# remote.net
KiCad netlist of a schematic drawn in EAGLE
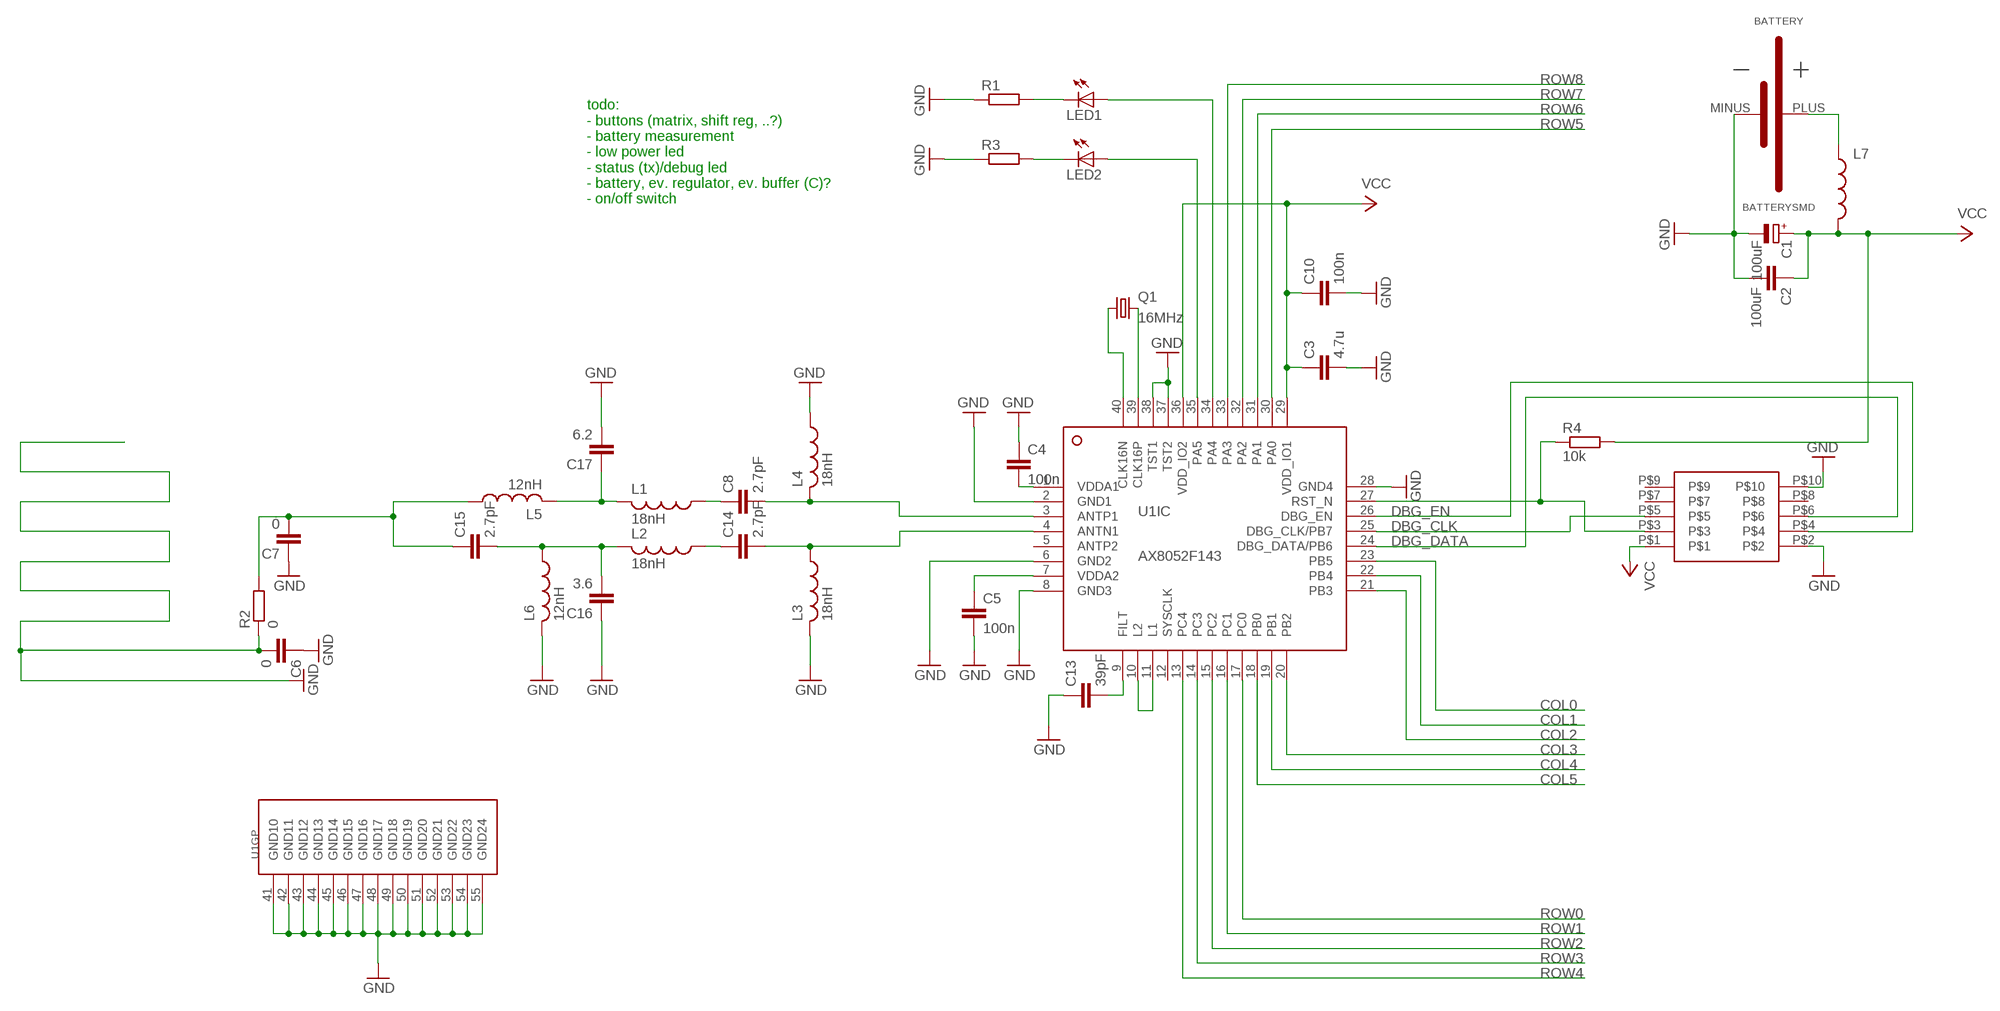
[diagram p0: schematic, sheet 1, part 1 of 2]
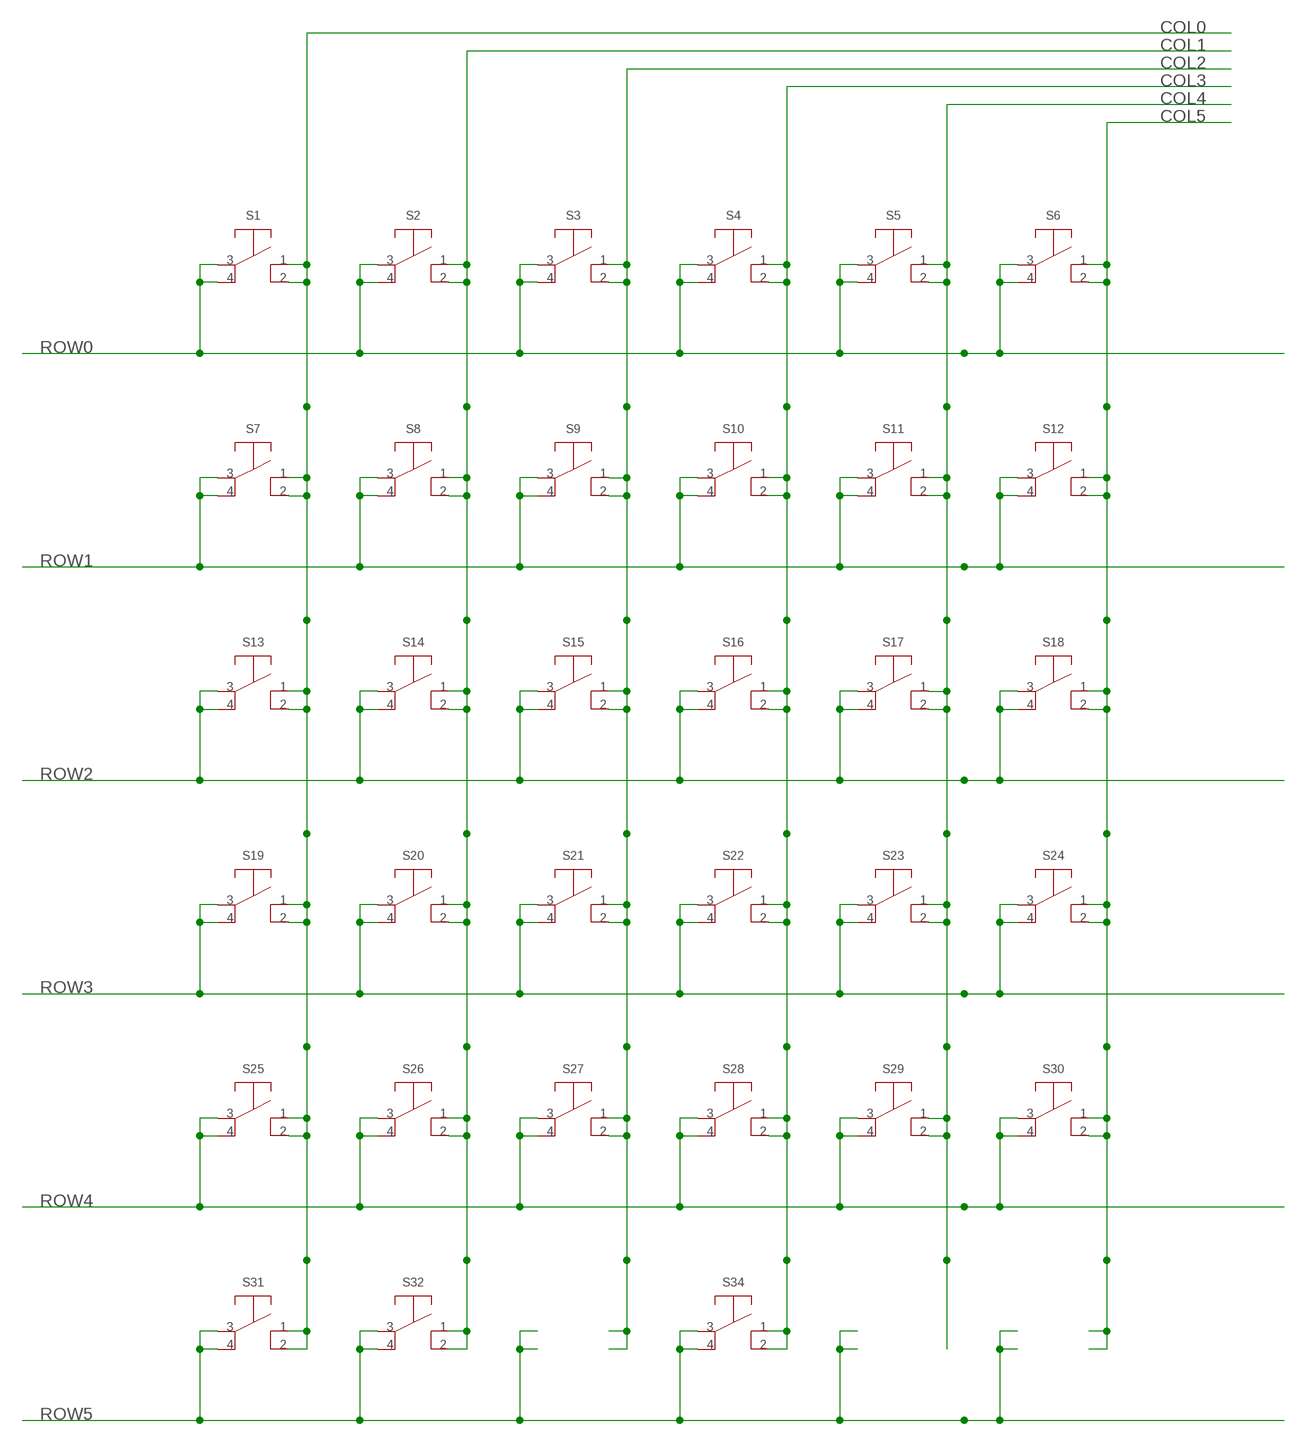
[diagram p1: schematic, sheet 1, part 2 of 2]

(export (version "E")
  (design (tool "Eeschema 10.0.6"))
  (components
    (comp (ref "BATTERY")
      (value "BATTERYSMD")
      (footprint "eagle-import:CR2032-SMD")
      (libsource (lib "eagle-import") (part "BATTERYSMD"))
    )
    (comp (ref "C1")
      (value "100uF")
      (footprint "eagle-import:PANASONIC_E")
      (libsource (lib "eagle-import") (part "CPOL-EUE"))
    )
    (comp (ref "C2")
      (value "100uF")
      (footprint "eagle-import:C1206K")
      (libsource (lib "eagle-import") (part "C-EUC1206K"))
    )
    (comp (ref "C3")
      (value "4.7u")
      (footprint "eagle-import:C0805")
      (libsource (lib "eagle-import") (part "C-EUC0805"))
    )
    (comp (ref "C4")
      (value "100n")
      (footprint "eagle-import:C0603")
      (libsource (lib "eagle-import") (part "C-EUC0603"))
    )
    (comp (ref "C5")
      (value "100n")
      (footprint "eagle-import:C0603")
      (libsource (lib "eagle-import") (part "C-EUC0603"))
    )
    (comp (ref "C6")
      (value "0")
      (footprint "eagle-import:C0805")
      (libsource (lib "eagle-import") (part "C-EUC0805"))
    )
    (comp (ref "C7")
      (value "0")
      (footprint "eagle-import:C0805")
      (libsource (lib "eagle-import") (part "C-EUC0805"))
    )
    (comp (ref "C8")
      (value "2.7pF")
      (footprint "eagle-import:C0805")
      (libsource (lib "eagle-import") (part "C-EUC0805"))
    )
    (comp (ref "C10")
      (value "100n")
      (footprint "eagle-import:C0603")
      (libsource (lib "eagle-import") (part "C-EUC0603"))
    )
    (comp (ref "C13")
      (value "39pF")
      (footprint "eagle-import:C0805")
      (libsource (lib "eagle-import") (part "C-EUC0805"))
    )
    (comp (ref "C14")
      (value "2.7pF")
      (footprint "eagle-import:C0805")
      (libsource (lib "eagle-import") (part "C-EUC0805"))
    )
    (comp (ref "C15")
      (value "2.7pF")
      (footprint "eagle-import:C0805")
      (libsource (lib "eagle-import") (part "C-EUC0805"))
    )
    (comp (ref "C16")
      (value "3.6")
      (footprint "eagle-import:C0805")
      (libsource (lib "eagle-import") (part "C-EUC0805"))
    )
    (comp (ref "C17")
      (value "6.2")
      (footprint "eagle-import:C0805")
      (libsource (lib "eagle-import") (part "C-EUC0805"))
    )
    (comp (ref "L1")
      (value "18nH")
      (footprint "eagle-import:C0603")
      (libsource (lib "eagle-import") (part "L-US0603"))
    )
    (comp (ref "L2")
      (value "18nH")
      (footprint "eagle-import:C0603")
      (libsource (lib "eagle-import") (part "L-US0603"))
    )
    (comp (ref "L3")
      (value "18nH")
      (footprint "eagle-import:C0603")
      (libsource (lib "eagle-import") (part "L-US0603"))
    )
    (comp (ref "L4")
      (value "18nH")
      (footprint "eagle-import:C0603")
      (libsource (lib "eagle-import") (part "L-US0603"))
    )
    (comp (ref "L5")
      (value "12nH")
      (footprint "eagle-import:C0603")
      (libsource (lib "eagle-import") (part "L-US0603"))
    )
    (comp (ref "L6")
      (value "12nH")
      (footprint "eagle-import:C0603")
      (libsource (lib "eagle-import") (part "L-US0603"))
    )
    (comp (ref "L7")
      (value "INDUCTORNPI75")
      (footprint "eagle-import:NPI75C")
      (libsource (lib "eagle-import") (part "INDUCTORNPI75"))
    )
    (comp (ref "LED1")
      (value "LEDCHIPLED_1206")
      (footprint "eagle-import:CHIPLED_1206")
      (libsource (lib "eagle-import") (part "LEDCHIPLED_1206"))
    )
    (comp (ref "LED2")
      (value "LEDCHIPLED_1206")
      (footprint "eagle-import:CHIPLED_1206")
      (libsource (lib "eagle-import") (part "LEDCHIPLED_1206"))
    )
    (comp (ref "Q1")
      (value "16MHz")
      (footprint "eagle-import:SM49")
      (libsource (lib "eagle-import") (part "CRYSTALSM49"))
    )
    (comp (ref "R1")
      (value "R-EU_R0603")
      (footprint "eagle-import:R0603")
      (libsource (lib "eagle-import") (part "R-EU_R0603"))
    )
    (comp (ref "R2")
      (value "0")
      (footprint "eagle-import:R0603")
      (libsource (lib "eagle-import") (part "R-EU_R0603"))
    )
    (comp (ref "R3")
      (value "R-EU_R0603")
      (footprint "eagle-import:R0603")
      (libsource (lib "eagle-import") (part "R-EU_R0603"))
    )
    (comp (ref "R4")
      (value "10k")
      (footprint "eagle-import:R0603")
      (libsource (lib "eagle-import") (part "R-EU_R0603"))
    )
    (comp (ref "S1")
      (value "SWITCHSMD")
      (footprint "eagle-import:TACTILE_SWITCH_FSM2JSMA")
      (libsource (lib "eagle-import") (part "SWITCHSMD"))
    )
    (comp (ref "S2")
      (value "SWITCHSMD")
      (footprint "eagle-import:TACTILE_SWITCH_FSM2JSMA")
      (libsource (lib "eagle-import") (part "SWITCHSMD"))
    )
    (comp (ref "S3")
      (value "SWITCHSMD")
      (footprint "eagle-import:TACTILE_SWITCH_FSM2JSMA")
      (libsource (lib "eagle-import") (part "SWITCHSMD"))
    )
    (comp (ref "S4")
      (value "SWITCHSMD")
      (footprint "eagle-import:TACTILE_SWITCH_FSM2JSMA")
      (libsource (lib "eagle-import") (part "SWITCHSMD"))
    )
    (comp (ref "S5")
      (value "SWITCHSMD")
      (footprint "eagle-import:TACTILE_SWITCH_FSM2JSMA")
      (libsource (lib "eagle-import") (part "SWITCHSMD"))
    )
    (comp (ref "S6")
      (value "SWITCHSMD")
      (footprint "eagle-import:TACTILE_SWITCH_FSM2JSMA")
      (libsource (lib "eagle-import") (part "SWITCHSMD"))
    )
    (comp (ref "S7")
      (value "SWITCHSMD")
      (footprint "eagle-import:TACTILE_SWITCH_FSM2JSMA")
      (libsource (lib "eagle-import") (part "SWITCHSMD"))
    )
    (comp (ref "S8")
      (value "SWITCHSMD")
      (footprint "eagle-import:TACTILE_SWITCH_FSM2JSMA")
      (libsource (lib "eagle-import") (part "SWITCHSMD"))
    )
    (comp (ref "S9")
      (value "SWITCHSMD")
      (footprint "eagle-import:TACTILE_SWITCH_FSM2JSMA")
      (libsource (lib "eagle-import") (part "SWITCHSMD"))
    )
    (comp (ref "S10")
      (value "SWITCHSMD")
      (footprint "eagle-import:TACTILE_SWITCH_FSM2JSMA")
      (libsource (lib "eagle-import") (part "SWITCHSMD"))
    )
    (comp (ref "S11")
      (value "SWITCHSMD")
      (footprint "eagle-import:TACTILE_SWITCH_FSM2JSMA")
      (libsource (lib "eagle-import") (part "SWITCHSMD"))
    )
    (comp (ref "S12")
      (value "SWITCHSMD")
      (footprint "eagle-import:TACTILE_SWITCH_FSM2JSMA")
      (libsource (lib "eagle-import") (part "SWITCHSMD"))
    )
    (comp (ref "S13")
      (value "SWITCHSMD")
      (footprint "eagle-import:TACTILE_SWITCH_FSM2JSMA")
      (libsource (lib "eagle-import") (part "SWITCHSMD"))
    )
    (comp (ref "S14")
      (value "SWITCHSMD")
      (footprint "eagle-import:TACTILE_SWITCH_FSM2JSMA")
      (libsource (lib "eagle-import") (part "SWITCHSMD"))
    )
    (comp (ref "S15")
      (value "SWITCHSMD")
      (footprint "eagle-import:TACTILE_SWITCH_FSM2JSMA")
      (libsource (lib "eagle-import") (part "SWITCHSMD"))
    )
    (comp (ref "S16")
      (value "SWITCHSMD")
      (footprint "eagle-import:TACTILE_SWITCH_FSM2JSMA")
      (libsource (lib "eagle-import") (part "SWITCHSMD"))
    )
    (comp (ref "S17")
      (value "SWITCHSMD")
      (footprint "eagle-import:TACTILE_SWITCH_FSM2JSMA")
      (libsource (lib "eagle-import") (part "SWITCHSMD"))
    )
    (comp (ref "S18")
      (value "SWITCHSMD")
      (footprint "eagle-import:TACTILE_SWITCH_FSM2JSMA")
      (libsource (lib "eagle-import") (part "SWITCHSMD"))
    )
    (comp (ref "S19")
      (value "SWITCHSMD")
      (footprint "eagle-import:TACTILE_SWITCH_FSM2JSMA")
      (libsource (lib "eagle-import") (part "SWITCHSMD"))
    )
    (comp (ref "S20")
      (value "SWITCHSMD")
      (footprint "eagle-import:TACTILE_SWITCH_FSM2JSMA")
      (libsource (lib "eagle-import") (part "SWITCHSMD"))
    )
    (comp (ref "S21")
      (value "SWITCHSMD")
      (footprint "eagle-import:TACTILE_SWITCH_FSM2JSMA")
      (libsource (lib "eagle-import") (part "SWITCHSMD"))
    )
    (comp (ref "S22")
      (value "SWITCHSMD")
      (footprint "eagle-import:TACTILE_SWITCH_FSM2JSMA")
      (libsource (lib "eagle-import") (part "SWITCHSMD"))
    )
    (comp (ref "S23")
      (value "SWITCHSMD")
      (footprint "eagle-import:TACTILE_SWITCH_FSM2JSMA")
      (libsource (lib "eagle-import") (part "SWITCHSMD"))
    )
    (comp (ref "S24")
      (value "SWITCHSMD")
      (footprint "eagle-import:TACTILE_SWITCH_FSM2JSMA")
      (libsource (lib "eagle-import") (part "SWITCHSMD"))
    )
    (comp (ref "S25")
      (value "SWITCHSMD")
      (footprint "eagle-import:TACTILE_SWITCH_FSM2JSMA")
      (libsource (lib "eagle-import") (part "SWITCHSMD"))
    )
    (comp (ref "S26")
      (value "SWITCHSMD")
      (footprint "eagle-import:TACTILE_SWITCH_FSM2JSMA")
      (libsource (lib "eagle-import") (part "SWITCHSMD"))
    )
    (comp (ref "S27")
      (value "SWITCHSMD")
      (footprint "eagle-import:TACTILE_SWITCH_FSM2JSMA")
      (libsource (lib "eagle-import") (part "SWITCHSMD"))
    )
    (comp (ref "S28")
      (value "SWITCHSMD")
      (footprint "eagle-import:TACTILE_SWITCH_FSM2JSMA")
      (libsource (lib "eagle-import") (part "SWITCHSMD"))
    )
    (comp (ref "S29")
      (value "SWITCHSMD")
      (footprint "eagle-import:TACTILE_SWITCH_FSM2JSMA")
      (libsource (lib "eagle-import") (part "SWITCHSMD"))
    )
    (comp (ref "S30")
      (value "SWITCHSMD")
      (footprint "eagle-import:TACTILE_SWITCH_FSM2JSMA")
      (libsource (lib "eagle-import") (part "SWITCHSMD"))
    )
    (comp (ref "S31")
      (value "SWITCHSMD")
      (footprint "eagle-import:TACTILE_SWITCH_FSM2JSMA")
      (libsource (lib "eagle-import") (part "SWITCHSMD"))
    )
    (comp (ref "S32")
      (value "SWITCHSMD")
      (footprint "eagle-import:TACTILE_SWITCH_FSM2JSMA")
      (libsource (lib "eagle-import") (part "SWITCHSMD"))
    )
    (comp (ref "S34")
      (value "SWITCHSMD")
      (footprint "eagle-import:TACTILE_SWITCH_FSM2JSMA")
      (libsource (lib "eagle-import") (part "SWITCHSMD"))
    )
    (comp (ref "U$2")
      (value "2X5PIN-CONNECTOR")
      (footprint "eagle-import:2X5PIN-CONNECTOR-SMD")
      (libsource (lib "eagle-import") (part "2X5PIN-CONNECTOR"))
    )
    (comp (ref "U1")
      (value "AX8052F143HS")
      (footprint "eagle-import:QFN40-H")
      (libsource (lib "eagle-import") (part "AX8052F143HS"))
    )
  )
  (nets
    (net (code "1") (name "/COL0") (class "Default")
      (node (ref "S1") (pin "P1") (pinfunction "P1_P1") (pintype "bidirectional"))
      (node (ref "S1") (pin "P2") (pinfunction "P2_P2") (pintype "bidirectional"))
      (node (ref "S13") (pin "P1") (pinfunction "P1_P1") (pintype "bidirectional"))
      (node (ref "S13") (pin "P2") (pinfunction "P2_P2") (pintype "bidirectional"))
      (node (ref "S19") (pin "P1") (pinfunction "P1_P1") (pintype "bidirectional"))
      (node (ref "S19") (pin "P2") (pinfunction "P2_P2") (pintype "bidirectional"))
      (node (ref "S25") (pin "P1") (pinfunction "P1_P1") (pintype "bidirectional"))
      (node (ref "S25") (pin "P2") (pinfunction "P2_P2") (pintype "bidirectional"))
      (node (ref "S31") (pin "P1") (pinfunction "P1_P1") (pintype "bidirectional"))
      (node (ref "S31") (pin "P2") (pinfunction "P2_P2") (pintype "bidirectional"))
      (node (ref "S7") (pin "P1") (pinfunction "P1_P1") (pintype "bidirectional"))
      (node (ref "S7") (pin "P2") (pinfunction "P2_P2") (pintype "bidirectional"))
      (node (ref "U1") (pin "23") (pinfunction "PB5_23") (pintype "bidirectional"))
    )
    (net (code "2") (name "/COL1") (class "Default")
      (node (ref "S14") (pin "P1") (pinfunction "P1_P1") (pintype "bidirectional"))
      (node (ref "S14") (pin "P2") (pinfunction "P2_P2") (pintype "bidirectional"))
      (node (ref "S2") (pin "P1") (pinfunction "P1_P1") (pintype "bidirectional"))
      (node (ref "S2") (pin "P2") (pinfunction "P2_P2") (pintype "bidirectional"))
      (node (ref "S20") (pin "P1") (pinfunction "P1_P1") (pintype "bidirectional"))
      (node (ref "S20") (pin "P2") (pinfunction "P2_P2") (pintype "bidirectional"))
      (node (ref "S26") (pin "P1") (pinfunction "P1_P1") (pintype "bidirectional"))
      (node (ref "S26") (pin "P2") (pinfunction "P2_P2") (pintype "bidirectional"))
      (node (ref "S32") (pin "P1") (pinfunction "P1_P1") (pintype "bidirectional"))
      (node (ref "S32") (pin "P2") (pinfunction "P2_P2") (pintype "bidirectional"))
      (node (ref "S8") (pin "P1") (pinfunction "P1_P1") (pintype "bidirectional"))
      (node (ref "S8") (pin "P2") (pinfunction "P2_P2") (pintype "bidirectional"))
      (node (ref "U1") (pin "22") (pinfunction "PB4_22") (pintype "bidirectional"))
    )
    (net (code "3") (name "/COL2") (class "Default")
      (node (ref "S15") (pin "P1") (pinfunction "P1_P1") (pintype "bidirectional"))
      (node (ref "S15") (pin "P2") (pinfunction "P2_P2") (pintype "bidirectional"))
      (node (ref "S21") (pin "P1") (pinfunction "P1_P1") (pintype "bidirectional"))
      (node (ref "S21") (pin "P2") (pinfunction "P2_P2") (pintype "bidirectional"))
      (node (ref "S27") (pin "P1") (pinfunction "P1_P1") (pintype "bidirectional"))
      (node (ref "S27") (pin "P2") (pinfunction "P2_P2") (pintype "bidirectional"))
      (node (ref "S3") (pin "P1") (pinfunction "P1_P1") (pintype "bidirectional"))
      (node (ref "S3") (pin "P2") (pinfunction "P2_P2") (pintype "bidirectional"))
      (node (ref "S9") (pin "P1") (pinfunction "P1_P1") (pintype "bidirectional"))
      (node (ref "S9") (pin "P2") (pinfunction "P2_P2") (pintype "bidirectional"))
      (node (ref "U1") (pin "21") (pinfunction "PB3_21") (pintype "bidirectional"))
    )
    (net (code "4") (name "/COL3") (class "Default")
      (node (ref "S10") (pin "P1") (pinfunction "P1_P1") (pintype "bidirectional"))
      (node (ref "S10") (pin "P2") (pinfunction "P2_P2") (pintype "bidirectional"))
      (node (ref "S16") (pin "P1") (pinfunction "P1_P1") (pintype "bidirectional"))
      (node (ref "S16") (pin "P2") (pinfunction "P2_P2") (pintype "bidirectional"))
      (node (ref "S22") (pin "P1") (pinfunction "P1_P1") (pintype "bidirectional"))
      (node (ref "S22") (pin "P2") (pinfunction "P2_P2") (pintype "bidirectional"))
      (node (ref "S28") (pin "P1") (pinfunction "P1_P1") (pintype "bidirectional"))
      (node (ref "S28") (pin "P2") (pinfunction "P2_P2") (pintype "bidirectional"))
      (node (ref "S34") (pin "P1") (pinfunction "P1_P1") (pintype "bidirectional"))
      (node (ref "S34") (pin "P2") (pinfunction "P2_P2") (pintype "bidirectional"))
      (node (ref "S4") (pin "P1") (pinfunction "P1_P1") (pintype "bidirectional"))
      (node (ref "S4") (pin "P2") (pinfunction "P2_P2") (pintype "bidirectional"))
      (node (ref "U1") (pin "20") (pinfunction "PB2_20") (pintype "bidirectional"))
    )
    (net (code "5") (name "/COL4") (class "Default")
      (node (ref "S11") (pin "P1") (pinfunction "P1_P1") (pintype "bidirectional"))
      (node (ref "S11") (pin "P2") (pinfunction "P2_P2") (pintype "bidirectional"))
      (node (ref "S17") (pin "P1") (pinfunction "P1_P1") (pintype "bidirectional"))
      (node (ref "S17") (pin "P2") (pinfunction "P2_P2") (pintype "bidirectional"))
      (node (ref "S23") (pin "P1") (pinfunction "P1_P1") (pintype "bidirectional"))
      (node (ref "S23") (pin "P2") (pinfunction "P2_P2") (pintype "bidirectional"))
      (node (ref "S29") (pin "P1") (pinfunction "P1_P1") (pintype "bidirectional"))
      (node (ref "S29") (pin "P2") (pinfunction "P2_P2") (pintype "bidirectional"))
      (node (ref "S5") (pin "P1") (pinfunction "P1_P1") (pintype "bidirectional"))
      (node (ref "S5") (pin "P2") (pinfunction "P2_P2") (pintype "bidirectional"))
      (node (ref "U1") (pin "19") (pinfunction "PB1_19") (pintype "bidirectional"))
    )
    (net (code "6") (name "/COL5") (class "Default")
      (node (ref "S12") (pin "P1") (pinfunction "P1_P1") (pintype "bidirectional"))
      (node (ref "S12") (pin "P2") (pinfunction "P2_P2") (pintype "bidirectional"))
      (node (ref "S18") (pin "P1") (pinfunction "P1_P1") (pintype "bidirectional"))
      (node (ref "S18") (pin "P2") (pinfunction "P2_P2") (pintype "bidirectional"))
      (node (ref "S24") (pin "P1") (pinfunction "P1_P1") (pintype "bidirectional"))
      (node (ref "S24") (pin "P2") (pinfunction "P2_P2") (pintype "bidirectional"))
      (node (ref "S30") (pin "P1") (pinfunction "P1_P1") (pintype "bidirectional"))
      (node (ref "S30") (pin "P2") (pinfunction "P2_P2") (pintype "bidirectional"))
      (node (ref "S6") (pin "P1") (pinfunction "P1_P1") (pintype "bidirectional"))
      (node (ref "S6") (pin "P2") (pinfunction "P2_P2") (pintype "bidirectional"))
      (node (ref "U1") (pin "18") (pinfunction "PB0_18") (pintype "bidirectional"))
    )
    (net (code "7") (name "/DBG_CLK") (class "Default")
      (node (ref "U$2") (pin "P$5") (pinfunction "P$5_P$5") (pintype "bidirectional"))
      (node (ref "U1") (pin "25") (pinfunction "DBG_CLK/PB7_25") (pintype "bidirectional"))
    )
    (net (code "8") (name "/DBG_DATA") (class "Default")
      (node (ref "U$2") (pin "P$6") (pinfunction "P$6_P$6") (pintype "bidirectional"))
      (node (ref "U1") (pin "24") (pinfunction "DBG_DATA/PB6_24") (pintype "bidirectional"))
    )
    (net (code "9") (name "/DBG_EN") (class "Default")
      (node (ref "U$2") (pin "P$4") (pinfunction "P$4_P$4") (pintype "bidirectional"))
      (node (ref "U1") (pin "26") (pinfunction "DBG_EN_26") (pintype "input"))
    )
    (net (code "10") (name "/ROW0") (class "Default")
      (node (ref "S1") (pin "P3") (pinfunction "P3_P3") (pintype "bidirectional"))
      (node (ref "S1") (pin "P4") (pinfunction "P4_P4") (pintype "bidirectional"))
      (node (ref "S2") (pin "P3") (pinfunction "P3_P3") (pintype "bidirectional"))
      (node (ref "S2") (pin "P4") (pinfunction "P4_P4") (pintype "bidirectional"))
      (node (ref "S3") (pin "P3") (pinfunction "P3_P3") (pintype "bidirectional"))
      (node (ref "S3") (pin "P4") (pinfunction "P4_P4") (pintype "bidirectional"))
      (node (ref "S4") (pin "P3") (pinfunction "P3_P3") (pintype "bidirectional"))
      (node (ref "S4") (pin "P4") (pinfunction "P4_P4") (pintype "bidirectional"))
      (node (ref "S5") (pin "P3") (pinfunction "P3_P3") (pintype "bidirectional"))
      (node (ref "S5") (pin "P4") (pinfunction "P4_P4") (pintype "bidirectional"))
      (node (ref "S6") (pin "P3") (pinfunction "P3_P3") (pintype "bidirectional"))
      (node (ref "S6") (pin "P4") (pinfunction "P4_P4") (pintype "bidirectional"))
      (node (ref "U1") (pin "17") (pinfunction "PC0_17") (pintype "bidirectional"))
    )
    (net (code "11") (name "/ROW1") (class "Default")
      (node (ref "S10") (pin "P3") (pinfunction "P3_P3") (pintype "bidirectional"))
      (node (ref "S10") (pin "P4") (pinfunction "P4_P4") (pintype "bidirectional"))
      (node (ref "S11") (pin "P3") (pinfunction "P3_P3") (pintype "bidirectional"))
      (node (ref "S11") (pin "P4") (pinfunction "P4_P4") (pintype "bidirectional"))
      (node (ref "S12") (pin "P3") (pinfunction "P3_P3") (pintype "bidirectional"))
      (node (ref "S12") (pin "P4") (pinfunction "P4_P4") (pintype "bidirectional"))
      (node (ref "S7") (pin "P3") (pinfunction "P3_P3") (pintype "bidirectional"))
      (node (ref "S7") (pin "P4") (pinfunction "P4_P4") (pintype "bidirectional"))
      (node (ref "S8") (pin "P3") (pinfunction "P3_P3") (pintype "bidirectional"))
      (node (ref "S8") (pin "P4") (pinfunction "P4_P4") (pintype "bidirectional"))
      (node (ref "S9") (pin "P3") (pinfunction "P3_P3") (pintype "bidirectional"))
      (node (ref "S9") (pin "P4") (pinfunction "P4_P4") (pintype "bidirectional"))
      (node (ref "U1") (pin "16") (pinfunction "PC1_16") (pintype "bidirectional"))
    )
    (net (code "12") (name "/ROW2") (class "Default")
      (node (ref "S13") (pin "P3") (pinfunction "P3_P3") (pintype "bidirectional"))
      (node (ref "S13") (pin "P4") (pinfunction "P4_P4") (pintype "bidirectional"))
      (node (ref "S14") (pin "P3") (pinfunction "P3_P3") (pintype "bidirectional"))
      (node (ref "S14") (pin "P4") (pinfunction "P4_P4") (pintype "bidirectional"))
      (node (ref "S15") (pin "P3") (pinfunction "P3_P3") (pintype "bidirectional"))
      (node (ref "S15") (pin "P4") (pinfunction "P4_P4") (pintype "bidirectional"))
      (node (ref "S16") (pin "P3") (pinfunction "P3_P3") (pintype "bidirectional"))
      (node (ref "S16") (pin "P4") (pinfunction "P4_P4") (pintype "bidirectional"))
      (node (ref "S17") (pin "P3") (pinfunction "P3_P3") (pintype "bidirectional"))
      (node (ref "S17") (pin "P4") (pinfunction "P4_P4") (pintype "bidirectional"))
      (node (ref "S18") (pin "P3") (pinfunction "P3_P3") (pintype "bidirectional"))
      (node (ref "S18") (pin "P4") (pinfunction "P4_P4") (pintype "bidirectional"))
      (node (ref "U1") (pin "15") (pinfunction "PC2_15") (pintype "bidirectional"))
    )
    (net (code "13") (name "/ROW3") (class "Default")
      (node (ref "S19") (pin "P3") (pinfunction "P3_P3") (pintype "bidirectional"))
      (node (ref "S19") (pin "P4") (pinfunction "P4_P4") (pintype "bidirectional"))
      (node (ref "S20") (pin "P3") (pinfunction "P3_P3") (pintype "bidirectional"))
      (node (ref "S20") (pin "P4") (pinfunction "P4_P4") (pintype "bidirectional"))
      (node (ref "S21") (pin "P3") (pinfunction "P3_P3") (pintype "bidirectional"))
      (node (ref "S21") (pin "P4") (pinfunction "P4_P4") (pintype "bidirectional"))
      (node (ref "S22") (pin "P3") (pinfunction "P3_P3") (pintype "bidirectional"))
      (node (ref "S22") (pin "P4") (pinfunction "P4_P4") (pintype "bidirectional"))
      (node (ref "S23") (pin "P3") (pinfunction "P3_P3") (pintype "bidirectional"))
      (node (ref "S23") (pin "P4") (pinfunction "P4_P4") (pintype "bidirectional"))
      (node (ref "S24") (pin "P3") (pinfunction "P3_P3") (pintype "bidirectional"))
      (node (ref "S24") (pin "P4") (pinfunction "P4_P4") (pintype "bidirectional"))
      (node (ref "U1") (pin "14") (pinfunction "PC3_14") (pintype "bidirectional"))
    )
    (net (code "14") (name "/ROW4") (class "Default")
      (node (ref "S25") (pin "P3") (pinfunction "P3_P3") (pintype "bidirectional"))
      (node (ref "S25") (pin "P4") (pinfunction "P4_P4") (pintype "bidirectional"))
      (node (ref "S26") (pin "P3") (pinfunction "P3_P3") (pintype "bidirectional"))
      (node (ref "S26") (pin "P4") (pinfunction "P4_P4") (pintype "bidirectional"))
      (node (ref "S27") (pin "P3") (pinfunction "P3_P3") (pintype "bidirectional"))
      (node (ref "S27") (pin "P4") (pinfunction "P4_P4") (pintype "bidirectional"))
      (node (ref "S28") (pin "P3") (pinfunction "P3_P3") (pintype "bidirectional"))
      (node (ref "S28") (pin "P4") (pinfunction "P4_P4") (pintype "bidirectional"))
      (node (ref "S29") (pin "P3") (pinfunction "P3_P3") (pintype "bidirectional"))
      (node (ref "S29") (pin "P4") (pinfunction "P4_P4") (pintype "bidirectional"))
      (node (ref "S30") (pin "P3") (pinfunction "P3_P3") (pintype "bidirectional"))
      (node (ref "S30") (pin "P4") (pinfunction "P4_P4") (pintype "bidirectional"))
      (node (ref "U1") (pin "13") (pinfunction "PC4_13") (pintype "bidirectional"))
    )
    (net (code "15") (name "/ROW5") (class "Default")
      (node (ref "S31") (pin "P3") (pinfunction "P3_P3") (pintype "bidirectional"))
      (node (ref "S31") (pin "P4") (pinfunction "P4_P4") (pintype "bidirectional"))
      (node (ref "S32") (pin "P3") (pinfunction "P3_P3") (pintype "bidirectional"))
      (node (ref "S32") (pin "P4") (pinfunction "P4_P4") (pintype "bidirectional"))
      (node (ref "S34") (pin "P3") (pinfunction "P3_P3") (pintype "bidirectional"))
      (node (ref "S34") (pin "P4") (pinfunction "P4_P4") (pintype "bidirectional"))
      (node (ref "U1") (pin "30") (pinfunction "PA0_30") (pintype "bidirectional"))
    )
    (net (code "16") (name "/ROW6") (class "Default")
      (node (ref "U1") (pin "31") (pinfunction "PA1_31") (pintype "bidirectional"))
    )
    (net (code "17") (name "/ROW7") (class "Default")
      (node (ref "U1") (pin "32") (pinfunction "PA2_32") (pintype "bidirectional"))
    )
    (net (code "18") (name "/ROW8") (class "Default")
      (node (ref "U1") (pin "33") (pinfunction "PA3_33") (pintype "bidirectional"))
    )
    (net (code "19") (name "GND") (class "Default")
      (node (ref "BATTERY") (pin "MINUS") (pinfunction "MINUS_MINUS") (pintype "power_in"))
      (node (ref "C1") (pin "-") (pinfunction "-_-") (pintype "passive"))
      (node (ref "C10") (pin "2") (pinfunction "2_2") (pintype "passive"))
      (node (ref "C13") (pin "1") (pinfunction "1_1") (pintype "passive"))
      (node (ref "C16") (pin "1") (pinfunction "1_1") (pintype "passive"))
      (node (ref "C17") (pin "2") (pinfunction "2_2") (pintype "passive"))
      (node (ref "C2") (pin "2") (pinfunction "2_2") (pintype "passive"))
      (node (ref "C3") (pin "2") (pinfunction "2_2") (pintype "passive"))
      (node (ref "C4") (pin "1") (pinfunction "1_1") (pintype "passive"))
      (node (ref "C5") (pin "2") (pinfunction "2_2") (pintype "passive"))
      (node (ref "C6") (pin "1") (pinfunction "1_1") (pintype "passive"))
      (node (ref "C6") (pin "2") (pinfunction "2_2") (pintype "passive"))
      (node (ref "C7") (pin "1") (pinfunction "1_1") (pintype "passive"))
      (node (ref "L3") (pin "2") (pinfunction "2_2") (pintype "passive"))
      (node (ref "L4") (pin "1") (pinfunction "1_1") (pintype "passive"))
      (node (ref "L6") (pin "2") (pinfunction "2_2") (pintype "passive"))
      (node (ref "R1") (pin "1") (pinfunction "1_1") (pintype "passive"))
      (node (ref "R2") (pin "1") (pinfunction "1_1") (pintype "passive"))
      (node (ref "R3") (pin "1") (pinfunction "1_1") (pintype "passive"))
      (node (ref "U$2") (pin "P$10") (pinfunction "P$10_P$10") (pintype "bidirectional"))
      (node (ref "U$2") (pin "P$2") (pinfunction "P$2_P$2") (pintype "bidirectional"))
      (node (ref "U1") (pin "2") (pinfunction "GND1_2") (pintype "power_in"))
      (node (ref "U1") (pin "28") (pinfunction "GND4_28") (pintype "power_in"))
      (node (ref "U1") (pin "37") (pinfunction "TST2_37") (pintype "bidirectional"))
      (node (ref "U1") (pin "38") (pinfunction "TST1_38") (pintype "power_in"))
      (node (ref "U1") (pin "41") (pinfunction "GND10_41") (pintype "power_in"))
      (node (ref "U1") (pin "42") (pinfunction "GND11_42") (pintype "power_in"))
      (node (ref "U1") (pin "43") (pinfunction "GND12_43") (pintype "power_in"))
      (node (ref "U1") (pin "44") (pinfunction "GND13_44") (pintype "power_in"))
      (node (ref "U1") (pin "45") (pinfunction "GND14_45") (pintype "power_in"))
      (node (ref "U1") (pin "46") (pinfunction "GND15_46") (pintype "power_in"))
      (node (ref "U1") (pin "47") (pinfunction "GND16_47") (pintype "power_in"))
      (node (ref "U1") (pin "48") (pinfunction "GND17_48") (pintype "power_in"))
      (node (ref "U1") (pin "49") (pinfunction "GND18_49") (pintype "power_in"))
      (node (ref "U1") (pin "50") (pinfunction "GND19_50") (pintype "power_in"))
      (node (ref "U1") (pin "51") (pinfunction "GND20_51") (pintype "power_in"))
      (node (ref "U1") (pin "52") (pinfunction "GND21_52") (pintype "power_in"))
      (node (ref "U1") (pin "53") (pinfunction "GND22_53") (pintype "power_in"))
      (node (ref "U1") (pin "54") (pinfunction "GND23_54") (pintype "power_in"))
      (node (ref "U1") (pin "55") (pinfunction "GND24_55") (pintype "power_in"))
      (node (ref "U1") (pin "6") (pinfunction "GND2_6") (pintype "passive"))
      (node (ref "U1") (pin "8") (pinfunction "GND3_8") (pintype "power_in"))
    )
    (net (code "20") (name "Net-(BATTERY-PadPLUS)") (class "Default")
      (node (ref "BATTERY") (pin "PLUS") (pinfunction "PLUS_PLUS") (pintype "power_in"))
      (node (ref "L7") (pin "1") (pinfunction "1_1") (pintype "passive"))
    )
    (net (code "21") (name "Net-(C8-Pad1)") (class "Default")
      (node (ref "C8") (pin "1") (pinfunction "1_1") (pintype "passive"))
      (node (ref "L1") (pin "1") (pinfunction "1_1") (pintype "passive"))
    )
    (net (code "22") (name "Net-(C14-Pad1)") (class "Default")
      (node (ref "C14") (pin "1") (pinfunction "1_1") (pintype "passive"))
      (node (ref "L2") (pin "1") (pinfunction "1_1") (pintype "passive"))
    )
    (net (code "23") (name "Net-(C15-Pad1)") (class "Default")
      (node (ref "C15") (pin "1") (pinfunction "1_1") (pintype "passive"))
      (node (ref "C7") (pin "2") (pinfunction "2_2") (pintype "passive"))
      (node (ref "L5") (pin "1") (pinfunction "1_1") (pintype "passive"))
      (node (ref "R2") (pin "2") (pinfunction "2_2") (pintype "passive"))
    )
    (net (code "24") (name "Net-(C15-Pad2)") (class "Default")
      (node (ref "C15") (pin "2") (pinfunction "2_2") (pintype "passive"))
      (node (ref "C16") (pin "2") (pinfunction "2_2") (pintype "passive"))
      (node (ref "L2") (pin "2") (pinfunction "2_2") (pintype "passive"))
      (node (ref "L6") (pin "1") (pinfunction "1_1") (pintype "passive"))
    )
    (net (code "25") (name "Net-(C17-Pad1)") (class "Default")
      (node (ref "C17") (pin "1") (pinfunction "1_1") (pintype "passive"))
      (node (ref "L1") (pin "2") (pinfunction "2_2") (pintype "passive"))
      (node (ref "L5") (pin "2") (pinfunction "2_2") (pintype "passive"))
    )
    (net (code "26") (name "Net-(LED1-PadC)") (class "Default")
      (node (ref "LED1") (pin "C") (pinfunction "C_C") (pintype "passive"))
      (node (ref "R1") (pin "2") (pinfunction "2_2") (pintype "passive"))
    )
    (net (code "27") (name "Net-(LED2-PadC)") (class "Default")
      (node (ref "LED2") (pin "C") (pinfunction "C_C") (pintype "passive"))
      (node (ref "R3") (pin "2") (pinfunction "2_2") (pintype "passive"))
    )
    (net (code "28") (name "Net-(U1B-ANTN1)") (class "Default")
      (node (ref "C14") (pin "2") (pinfunction "2_2") (pintype "passive"))
      (node (ref "L3") (pin "1") (pinfunction "1_1") (pintype "passive"))
      (node (ref "U1") (pin "4") (pinfunction "ANTN1_4") (pintype "power_in"))
    )
    (net (code "29") (name "Net-(U1B-ANTP1)") (class "Default")
      (node (ref "C8") (pin "2") (pinfunction "2_2") (pintype "passive"))
      (node (ref "L4") (pin "2") (pinfunction "2_2") (pintype "passive"))
      (node (ref "U1") (pin "3") (pinfunction "ANTP1_3") (pintype "power_in"))
    )
    (net (code "30") (name "Net-(U1B-CLK16N)") (class "Default")
      (node (ref "Q1") (pin "1") (pinfunction "1_1") (pintype "passive"))
      (node (ref "U1") (pin "40") (pinfunction "CLK16N_40") (pintype "passive"))
    )
    (net (code "31") (name "Net-(U1B-CLK16P)") (class "Default")
      (node (ref "Q1") (pin "2") (pinfunction "2_2") (pintype "passive"))
      (node (ref "U1") (pin "39") (pinfunction "CLK16P_39") (pintype "passive"))
    )
    (net (code "32") (name "Net-(U1B-FILT)") (class "Default")
      (node (ref "C13") (pin "2") (pinfunction "2_2") (pintype "passive"))
      (node (ref "U1") (pin "9") (pinfunction "FILT_9") (pintype "passive"))
    )
    (net (code "33") (name "Net-(U1B-L1)") (class "Default")
      (node (ref "U1") (pin "10") (pinfunction "L2_10") (pintype "passive"))
      (node (ref "U1") (pin "11") (pinfunction "L1_11") (pintype "input"))
    )
    (net (code "34") (name "Net-(U1B-PA4)") (class "Default")
      (node (ref "LED1") (pin "A") (pinfunction "A_A") (pintype "passive"))
      (node (ref "U1") (pin "34") (pinfunction "PA4_34") (pintype "bidirectional"))
    )
    (net (code "35") (name "Net-(U1B-PA5)") (class "Default")
      (node (ref "LED2") (pin "A") (pinfunction "A_A") (pintype "passive"))
      (node (ref "U1") (pin "35") (pinfunction "PA5_35") (pintype "bidirectional"))
    )
    (net (code "36") (name "Net-(U1B-RST_N)") (class "Default")
      (node (ref "R4") (pin "1") (pinfunction "1_1") (pintype "passive"))
      (node (ref "U$2") (pin "P$3") (pinfunction "P$3_P$3") (pintype "bidirectional"))
      (node (ref "U1") (pin "27") (pinfunction "RST_N_27") (pintype "input"))
    )
    (net (code "37") (name "Net-(U1B-VDDA1)") (class "Default")
      (node (ref "C4") (pin "2") (pinfunction "2_2") (pintype "passive"))
      (node (ref "U1") (pin "1") (pinfunction "VDDA1_1") (pintype "power_in"))
    )
    (net (code "38") (name "Net-(U1B-VDDA2)") (class "Default")
      (node (ref "C5") (pin "1") (pinfunction "1_1") (pintype "passive"))
      (node (ref "U1") (pin "7") (pinfunction "VDDA2_7") (pintype "power_in"))
    )
    (net (code "39") (name "VCC") (class "Default")
      (node (ref "C1") (pin "+") (pinfunction "+_+") (pintype "passive"))
      (node (ref "C10") (pin "1") (pinfunction "1_1") (pintype "passive"))
      (node (ref "C2") (pin "1") (pinfunction "1_1") (pintype "passive"))
      (node (ref "C3") (pin "1") (pinfunction "1_1") (pintype "passive"))
      (node (ref "L7") (pin "2") (pinfunction "2_2") (pintype "passive"))
      (node (ref "R4") (pin "2") (pinfunction "2_2") (pintype "passive"))
      (node (ref "U$2") (pin "P$1") (pinfunction "P$1_P$1") (pintype "bidirectional"))
      (node (ref "U1") (pin "29") (pinfunction "VDD_IO1_29") (pintype "power_in"))
      (node (ref "U1") (pin "36") (pinfunction "VDD_IO2_36") (pintype "bidirectional"))
    )
    (net (code "40") (name "unconnected-(U$2-PadP$7)") (class "Default")
      (node (ref "U$2") (pin "P$7") (pinfunction "P$7_P$7") (pintype "bidirectional"))
    )
    (net (code "41") (name "unconnected-(U$2-PadP$8)") (class "Default")
      (node (ref "U$2") (pin "P$8") (pinfunction "P$8_P$8") (pintype "bidirectional"))
    )
    (net (code "42") (name "unconnected-(U$2-PadP$9)") (class "Default")
      (node (ref "U$2") (pin "P$9") (pinfunction "P$9_P$9") (pintype "bidirectional"))
    )
    (net (code "43") (name "unconnected-(U1B-ANTP2-Pad5)") (class "Default")
      (node (ref "U1") (pin "5") (pinfunction "ANTP2_5") (pintype "passive"))
    )
    (net (code "44") (name "unconnected-(U1B-SYSCLK-Pad12)") (class "Default")
      (node (ref "U1") (pin "12") (pinfunction "SYSCLK_12") (pintype "output"))
    )
  )
)
